# ETH_HMI.net
KiCad netlist of a schematic drawn in Altium Designer
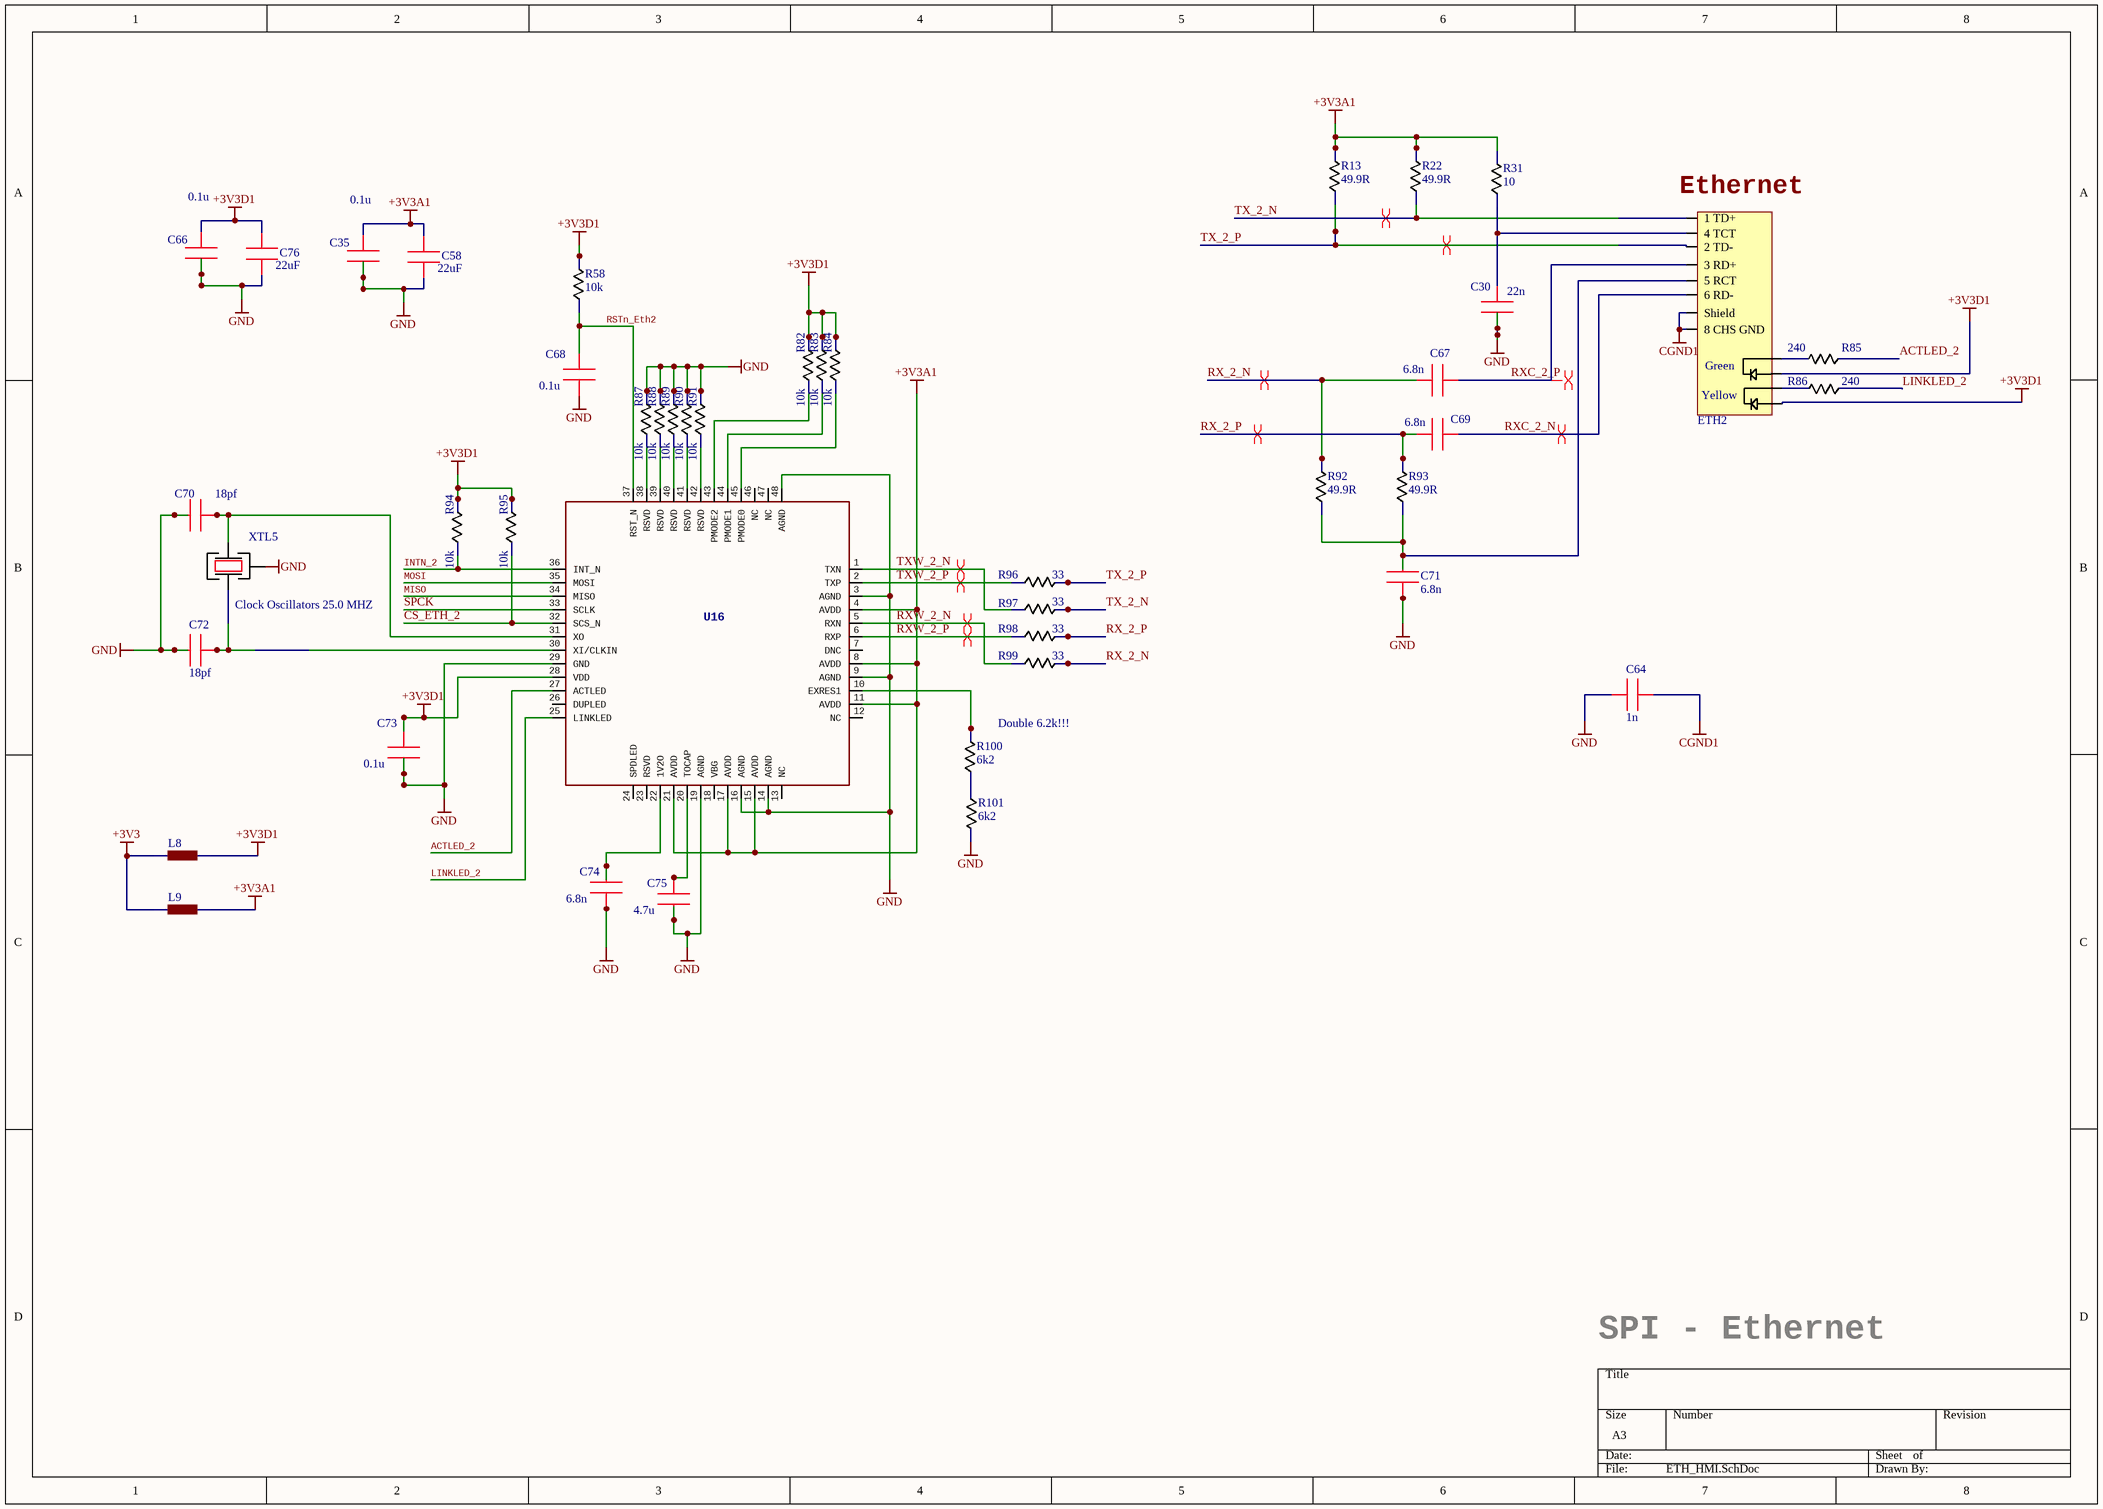
[diagram p0: ETH_HMI.SchDoc]

(export (version "E")
  (design (tool "Eeschema 10.0.6"))
  (components
    (comp (ref "C30")
      (value "22n")
      (footprint "0603")
      (fields (field (name "PART NUMBER") "GRM188R71H223KA01D"))
      (libsource (lib "kontr") (part "0603 CAP"))
    )
    (comp (ref "C35")
      (value "0.1u")
      (footprint "0603")
      (fields (field (name "PART NUMBER") "GRM188R72A104KA35D"))
      (libsource (lib "kontr") (part "0603 CAP"))
    )
    (comp (ref "C58")
      (value "22uF")
      (footprint "1206")
      (fields (field (name "PART NUMBER") "CC206KKX5R7BB226"))
      (libsource (lib "") (part "0805 Cap_1"))
    )
    (comp (ref "C64")
      (value "1n")
      (footprint "1206")
      (fields (field (name "PART NUMBER") "CC1206KKX7RDBB102"))
      (libsource (lib "kontr") (part "0603 CAP"))
    )
    (comp (ref "C66")
      (value "0.1u")
      (footprint "0603")
      (fields (field (name "PART NUMBER") "GRM188R72A104KA35D"))
      (libsource (lib "kontr") (part "0603 CAP"))
    )
    (comp (ref "C67")
      (value "6.8n")
      (footprint "0603")
      (fields (field (name "PART NUMBER") "CC0603KRX7R9BB682"))
      (libsource (lib "") (part "0603 CAP_1"))
    )
    (comp (ref "C68")
      (value "0.1u")
      (footprint "0603")
      (fields (field (name "PART NUMBER") "GRM188R72A104KA35D"))
      (libsource (lib "kontr") (part "0603 CAP"))
    )
    (comp (ref "C69")
      (value "6.8n")
      (footprint "0603")
      (fields (field (name "PART NUMBER") "CC0603KRX7R9BB682"))
      (libsource (lib "") (part "0603 CAP_1"))
    )
    (comp (ref "C70")
      (value "18pf")
      (footprint "0603")
      (fields (field (name "PART NUMBER") "GRM1885C1H180JA01D"))
      (libsource (lib "") (part "0603 CAP_1"))
    )
    (comp (ref "C71")
      (value "6.8n")
      (footprint "0603")
      (fields (field (name "PART NUMBER") "CC0603KRX7R9BB682"))
      (libsource (lib "kontr") (part "0603 CAP"))
    )
    (comp (ref "C72")
      (value "18pf")
      (footprint "0603")
      (fields (field (name "PART NUMBER") "GRM1885C1H180JA01D"))
      (libsource (lib "") (part "0603 CAP_1"))
    )
    (comp (ref "C73")
      (value "0.1u")
      (footprint "0603")
      (fields (field (name "PART NUMBER") "GRM188R72A104KA35D"))
      (libsource (lib "kontr") (part "0603 CAP"))
    )
    (comp (ref "C74")
      (value "6.8n")
      (footprint "0603")
      (fields (field (name "PART NUMBER") "CC0603KRX7R9BB682"))
      (libsource (lib "kontr") (part "0603 CAP"))
    )
    (comp (ref "C75")
      (value "4.7u")
      (footprint "0603")
      (fields (field (name "PART NUMBER") "CC0603KRX5R7BB475"))
      (libsource (lib "kontr") (part "0603 CAP"))
    )
    (comp (ref "C76")
      (value "22uF")
      (footprint "1206")
      (fields (field (name "PART NUMBER") "CC206KKX5R7BB226"))
      (libsource (lib "kontr") (part "0805 Cap"))
    )
    (comp (ref "ETH2")
      (value "~")
      (footprint "RJ45")
      (fields (field (name "PART NUMBER") "J0011D21BNL"))
      (libsource (lib "kontr") (part "J0011D21BNL"))
    )
    (comp (ref "L8")
      (value "~")
      (footprint "0805")
      (fields (field (name "PART NUMBER") "BLM41PG102SN1L"))
      (libsource (lib "kontr") (part "BLM21PG220SN1D"))
    )
    (comp (ref "L9")
      (value "~")
      (footprint "0805")
      (fields (field (name "PART NUMBER") "BLM41PG102SN1L"))
      (libsource (lib "kontr") (part "BLM21PG220SN1D"))
    )
    (comp (ref "R13")
      (value "49.9R")
      (footprint "0603")
      (fields (field (name "PART NUMBER") "RC0603FR-0749R9"))
      (libsource (lib "kontr") (part "0603 RES"))
    )
    (comp (ref "R22")
      (value "49.9R")
      (footprint "0603")
      (fields (field (name "PART NUMBER") "RC0603FR-0749R9"))
      (libsource (lib "kontr") (part "0603 RES"))
    )
    (comp (ref "R31")
      (value "10")
      (footprint "0603")
      (fields (field (name "PART NUMBER") "CRCW060310R0FKEA"))
      (libsource (lib "kontr") (part "0603 RES"))
    )
    (comp (ref "R58")
      (value "10k")
      (footprint "0603")
      (fields (field (name "PART NUMBER") "RC0603JR-0710K"))
      (libsource (lib "kontr") (part "0603 RES"))
    )
    (comp (ref "R82")
      (value "10k")
      (footprint "0603")
      (fields (field (name "PART NUMBER") "RC0603JR-0710K"))
      (libsource (lib "kontr") (part "0603 RES"))
    )
    (comp (ref "R83")
      (value "10k")
      (footprint "0603")
      (fields (field (name "PART NUMBER") "RC0603JR-0710K"))
      (libsource (lib "kontr") (part "0603 RES"))
    )
    (comp (ref "R84")
      (value "10k")
      (footprint "0603")
      (fields (field (name "PART NUMBER") "RC0603JR-0710K"))
      (libsource (lib "kontr") (part "0603 RES"))
    )
    (comp (ref "R85")
      (value "240")
      (footprint "0603")
      (fields (field (name "PART NUMBER") "RC0603FR-07240RL"))
      (libsource (lib "kontr") (part "0603 RES"))
    )
    (comp (ref "R86")
      (value "240")
      (footprint "0603")
      (fields (field (name "PART NUMBER") "RC0603FR-07240RL"))
      (libsource (lib "kontr") (part "0603 RES"))
    )
    (comp (ref "R87")
      (value "10k")
      (footprint "0603")
      (fields (field (name "PART NUMBER") "RC0603JR-0710K"))
      (libsource (lib "kontr") (part "0603 RES"))
    )
    (comp (ref "R88")
      (value "10k")
      (footprint "0603")
      (fields (field (name "PART NUMBER") "RC0603JR-0710K"))
      (libsource (lib "kontr") (part "0603 RES"))
    )
    (comp (ref "R89")
      (value "10k")
      (footprint "0603")
      (fields (field (name "PART NUMBER") "RC0603JR-0710K"))
      (libsource (lib "kontr") (part "0603 RES"))
    )
    (comp (ref "R90")
      (value "10k")
      (footprint "0603")
      (fields (field (name "PART NUMBER") "RC0603JR-0710K"))
      (libsource (lib "kontr") (part "0603 RES"))
    )
    (comp (ref "R91")
      (value "10k")
      (footprint "0603")
      (fields (field (name "PART NUMBER") "RC0603JR-0710K"))
      (libsource (lib "kontr") (part "0603 RES"))
    )
    (comp (ref "R92")
      (value "49.9R")
      (footprint "0603")
      (fields (field (name "PART NUMBER") "RC0603FR-0749R9"))
      (libsource (lib "kontr") (part "0603 RES"))
    )
    (comp (ref "R93")
      (value "49.9R")
      (footprint "0603")
      (fields (field (name "PART NUMBER") "RC0603FR-0749R9"))
      (libsource (lib "kontr") (part "0603 RES"))
    )
    (comp (ref "R94")
      (value "10k")
      (footprint "0603")
      (fields (field (name "PART NUMBER") "RC0603JR-0710K"))
      (libsource (lib "kontr") (part "0603 RES"))
    )
    (comp (ref "R95")
      (value "10k")
      (footprint "0603")
      (fields (field (name "PART NUMBER") "RC0603JR-0710K"))
      (libsource (lib "kontr") (part "0603 RES"))
    )
    (comp (ref "R96")
      (value "33")
      (footprint "0603")
      (fields (field (name "PART NUMBER") "RC0603FR-0733RL"))
      (libsource (lib "kontr") (part "0603 RES"))
    )
    (comp (ref "R97")
      (value "33")
      (footprint "0603")
      (fields (field (name "PART NUMBER") "RC0603FR-0733RL"))
      (libsource (lib "kontr") (part "0603 RES"))
    )
    (comp (ref "R98")
      (value "33")
      (footprint "0603")
      (fields (field (name "PART NUMBER") "RC0603FR-0733RL"))
      (libsource (lib "kontr") (part "0603 RES"))
    )
    (comp (ref "R99")
      (value "33")
      (footprint "0603")
      (fields (field (name "PART NUMBER") "RC0603FR-0733RL"))
      (libsource (lib "kontr") (part "0603 RES"))
    )
    (comp (ref "R100")
      (value "6k2")
      (footprint "0603")
      (fields (field (name "PART NUMBER") "RC0603JR-076K2L"))
      (libsource (lib "kontr") (part "0603 RES"))
    )
    (comp (ref "R101")
      (value "6k2")
      (footprint "0603")
      (fields (field (name "PART NUMBER") "RC0603JR-076K2L"))
      (libsource (lib "kontr") (part "Resistor 0805"))
    )
    (comp (ref "U16")
      (value "~")
      (footprint "LQFP 48")
      (fields (field (name "PART NUMBER") "W5500"))
      (libsource (lib "W5500") (part "W5500"))
    )
    (comp (ref "XTL5")
      (value "~")
      (footprint "KX-7 XTAL")
      (fields
        (field (name "PART DESCRIPTION") "Clock Oscillators 25.0 MHZ")
        (field (name "PART NUMBER") "Geyer KX-7 25.0 MHz")
      )
      (libsource (lib "kontr") (part "KX-7"))
    )
  )
  (nets
    (net (code "1") (name "+3V3") (class "Default")
      (node (ref "L8") (pin "1") (pintype "passive"))
      (node (ref "L9") (pin "1") (pintype "passive"))
    )
    (net (code "2") (name "+3V3A1") (class "Default")
      (node (ref "C35") (pin "1") (pinfunction "1_1") (pintype "passive"))
      (node (ref "C58") (pin "2") (pinfunction "2_2") (pintype "passive"))
      (node (ref "L9") (pin "2") (pintype "passive"))
      (node (ref "R13") (pin "2") (pintype "passive"))
      (node (ref "R22") (pin "2") (pintype "passive"))
      (node (ref "R31") (pin "2") (pintype "passive"))
      (node (ref "U16") (pin "11") (pinfunction "AVDD_11") (pintype "passive"))
      (node (ref "U16") (pin "15") (pinfunction "AVDD_15") (pintype "passive"))
      (node (ref "U16") (pin "17") (pinfunction "AVDD_17") (pintype "passive"))
      (node (ref "U16") (pin "21") (pinfunction "AVDD_21") (pintype "passive"))
      (node (ref "U16") (pin "4") (pinfunction "AVDD_4") (pintype "passive"))
      (node (ref "U16") (pin "8") (pinfunction "AVDD_8") (pintype "passive"))
    )
    (net (code "3") (name "+3V3D1") (class "Default")
      (node (ref "C66") (pin "1") (pinfunction "1_1") (pintype "passive"))
      (node (ref "C73") (pin "1") (pinfunction "1_1") (pintype "passive"))
      (node (ref "C76") (pin "2") (pinfunction "2_2") (pintype "passive"))
      (node (ref "ETH2") (pin "12") (pinfunction "LDYE_12") (pintype "passive"))
      (node (ref "ETH2") (pin "9") (pinfunction "LDGr_9") (pintype "passive"))
      (node (ref "L8") (pin "2") (pintype "passive"))
      (node (ref "R58") (pin "2") (pintype "passive"))
      (node (ref "R82") (pin "2") (pintype "passive"))
      (node (ref "R83") (pin "2") (pintype "passive"))
      (node (ref "R84") (pin "2") (pintype "passive"))
      (node (ref "R94") (pin "2") (pintype "passive"))
      (node (ref "R95") (pin "2") (pintype "passive"))
      (node (ref "U16") (pin "28") (pinfunction "VDD_28") (pintype "passive"))
    )
    (net (code "4") (name "/ACTLED_2") (class "Default")
      (node (ref "R85") (pin "1") (pintype "passive"))
      (node (ref "U16") (pin "27") (pinfunction "ACTLED_27") (pintype "passive"))
    )
    (net (code "5") (name "/CS_ETH_2") (class "Default")
      (node (ref "R95") (pin "1") (pintype "passive"))
      (node (ref "U16") (pin "32") (pinfunction "SCS_N_32") (pintype "passive"))
    )
    (net (code "6") (name "/INTN_2") (class "Default")
      (node (ref "R94") (pin "1") (pintype "passive"))
      (node (ref "U16") (pin "36") (pinfunction "INT_N_36") (pintype "passive"))
    )
    (net (code "7") (name "/LINKLED_2") (class "Default")
      (node (ref "R86") (pin "1") (pintype "passive"))
      (node (ref "U16") (pin "25") (pinfunction "LINKLED_25") (pintype "passive"))
    )
    (net (code "8") (name "/MISO") (class "Default")
      (node (ref "U16") (pin "34") (pinfunction "MISO_34") (pintype "passive"))
    )
    (net (code "9") (name "/MOSI") (class "Default")
      (node (ref "U16") (pin "35") (pinfunction "MOSI_35") (pintype "passive"))
    )
    (net (code "10") (name "/RSTn_Eth2") (class "Default")
      (node (ref "C68") (pin "1") (pinfunction "1_1") (pintype "passive"))
      (node (ref "R58") (pin "1") (pintype "passive"))
      (node (ref "U16") (pin "37") (pinfunction "RST_N_37") (pintype "passive"))
    )
    (net (code "11") (name "/RXC_2_N") (class "Default")
      (node (ref "C69") (pin "2") (pinfunction "2_2") (pintype "passive"))
      (node (ref "ETH2") (pin "6") (pinfunction "6_RD-_6") (pintype "passive"))
    )
    (net (code "12") (name "/RXC_2_P") (class "Default")
      (node (ref "C67") (pin "2") (pinfunction "2_2") (pintype "passive"))
      (node (ref "ETH2") (pin "3") (pinfunction "3_RD+_3") (pintype "passive"))
    )
    (net (code "13") (name "/RXW_2_N") (class "Default")
      (node (ref "R99") (pin "1") (pintype "passive"))
      (node (ref "U16") (pin "5") (pinfunction "RXN_5") (pintype "passive"))
    )
    (net (code "14") (name "/RXW_2_P") (class "Default")
      (node (ref "R98") (pin "1") (pintype "passive"))
      (node (ref "U16") (pin "6") (pinfunction "RXP_6") (pintype "passive"))
    )
    (net (code "15") (name "/RX_2_N") (class "Default")
      (node (ref "C67") (pin "1") (pinfunction "1_1") (pintype "passive"))
      (node (ref "R92") (pin "2") (pintype "passive"))
      (node (ref "R99") (pin "2") (pintype "passive"))
    )
    (net (code "16") (name "/RX_2_P") (class "Default")
      (node (ref "C69") (pin "1") (pinfunction "1_1") (pintype "passive"))
      (node (ref "R93") (pin "2") (pintype "passive"))
      (node (ref "R98") (pin "2") (pintype "passive"))
    )
    (net (code "17") (name "/SPCK") (class "Default")
      (node (ref "U16") (pin "33") (pinfunction "SCLK_33") (pintype "passive"))
    )
    (net (code "18") (name "/TXW_2_N") (class "Default")
      (node (ref "R97") (pin "1") (pintype "passive"))
      (node (ref "U16") (pin "1") (pinfunction "TXN_1") (pintype "passive"))
    )
    (net (code "19") (name "/TXW_2_P") (class "Default")
      (node (ref "R96") (pin "1") (pintype "passive"))
      (node (ref "U16") (pin "2") (pinfunction "TXP_2") (pintype "passive"))
    )
    (net (code "20") (name "/TX_2_N") (class "Default")
      (node (ref "ETH2") (pin "1") (pinfunction "1_TD+_1") (pintype "passive"))
      (node (ref "R22") (pin "1") (pintype "passive"))
      (node (ref "R97") (pin "2") (pintype "passive"))
    )
    (net (code "21") (name "/TX_2_P") (class "Default")
      (node (ref "ETH2") (pin "2") (pinfunction "2_TD-_2") (pintype "passive"))
      (node (ref "R13") (pin "1") (pintype "passive"))
      (node (ref "R96") (pin "2") (pintype "passive"))
    )
    (net (code "22") (name "CGND1") (class "Default")
      (node (ref "C64") (pin "2") (pinfunction "2_2") (pintype "passive"))
      (node (ref "ETH2") (pin "8") (pinfunction "8_CHS_GND_8") (pintype "passive"))
      (node (ref "ETH2") (pin "SHIELD") (pinfunction "Shield_SHIELD") (pintype "passive"))
    )
    (net (code "23") (name "GND") (class "Default")
      (node (ref "C30") (pin "2") (pinfunction "2_2") (pintype "passive"))
      (node (ref "C35") (pin "2") (pinfunction "2_2") (pintype "passive"))
      (node (ref "C58") (pin "1") (pinfunction "1_1") (pintype "passive"))
      (node (ref "C64") (pin "1") (pinfunction "1_1") (pintype "passive"))
      (node (ref "C66") (pin "2") (pinfunction "2_2") (pintype "passive"))
      (node (ref "C68") (pin "2") (pinfunction "2_2") (pintype "passive"))
      (node (ref "C70") (pin "1") (pinfunction "1_1") (pintype "passive"))
      (node (ref "C71") (pin "2") (pinfunction "2_2") (pintype "passive"))
      (node (ref "C72") (pin "1") (pinfunction "1_1") (pintype "passive"))
      (node (ref "C73") (pin "2") (pinfunction "2_2") (pintype "passive"))
      (node (ref "C74") (pin "2") (pinfunction "2_2") (pintype "passive"))
      (node (ref "C75") (pin "2") (pinfunction "2_2") (pintype "passive"))
      (node (ref "C76") (pin "1") (pinfunction "1_1") (pintype "passive"))
      (node (ref "R101") (pin "2") (pintype "passive"))
      (node (ref "R87") (pin "2") (pintype "passive"))
      (node (ref "R88") (pin "2") (pintype "passive"))
      (node (ref "R89") (pin "2") (pintype "passive"))
      (node (ref "R90") (pin "2") (pintype "passive"))
      (node (ref "R91") (pin "2") (pintype "passive"))
      (node (ref "U16") (pin "14") (pinfunction "AGND_14") (pintype "passive"))
      (node (ref "U16") (pin "16") (pinfunction "AGND_16") (pintype "passive"))
      (node (ref "U16") (pin "19") (pinfunction "AGND_19") (pintype "passive"))
      (node (ref "U16") (pin "29") (pinfunction "GND_29") (pintype "passive"))
      (node (ref "U16") (pin "3") (pinfunction "AGND_3") (pintype "passive"))
      (node (ref "U16") (pin "48") (pinfunction "AGND_48") (pintype "passive"))
      (node (ref "U16") (pin "9") (pinfunction "AGND_9") (pintype "passive"))
      (node (ref "XTL5") (pin "2") (pinfunction "2_2") (pintype "passive"))
    )
    (net (code "24") (name "Net-(ETH2-4_TCT)") (class "Default")
      (node (ref "C30") (pin "1") (pinfunction "1_1") (pintype "passive"))
      (node (ref "ETH2") (pin "4") (pinfunction "4_TCT_4") (pintype "passive"))
      (node (ref "R31") (pin "1") (pintype "passive"))
    )
    (net (code "25") (name "Net-(ETH2-5_RCT)") (class "Default")
      (node (ref "C71") (pin "1") (pinfunction "1_1") (pintype "passive"))
      (node (ref "ETH2") (pin "5") (pinfunction "5_RCT_5") (pintype "passive"))
      (node (ref "R92") (pin "1") (pintype "passive"))
      (node (ref "R93") (pin "1") (pintype "passive"))
    )
    (net (code "26") (name "Net-(ETH2-LDGr-Pad10)") (class "Default")
      (node (ref "ETH2") (pin "10") (pinfunction "LDGr_10") (pintype "passive"))
      (node (ref "R85") (pin "2") (pintype "passive"))
    )
    (net (code "27") (name "Net-(ETH2-LDYE-Pad11)") (class "Default")
      (node (ref "ETH2") (pin "11") (pinfunction "LDYE_11") (pintype "passive"))
      (node (ref "R86") (pin "2") (pintype "passive"))
    )
    (net (code "28") (name "Net-(R87-Pad1)") (class "Default")
      (node (ref "R87") (pin "1") (pintype "passive"))
      (node (ref "U16") (pin "38") (pinfunction "RSVD_38") (pintype "passive"))
    )
    (net (code "29") (name "Net-(R88-Pad1)") (class "Default")
      (node (ref "R88") (pin "1") (pintype "passive"))
      (node (ref "U16") (pin "39") (pinfunction "RSVD_39") (pintype "passive"))
    )
    (net (code "30") (name "Net-(R89-Pad1)") (class "Default")
      (node (ref "R89") (pin "1") (pintype "passive"))
      (node (ref "U16") (pin "40") (pinfunction "RSVD_40") (pintype "passive"))
    )
    (net (code "31") (name "Net-(R90-Pad1)") (class "Default")
      (node (ref "R90") (pin "1") (pintype "passive"))
      (node (ref "U16") (pin "41") (pinfunction "RSVD_41") (pintype "passive"))
    )
    (net (code "32") (name "Net-(R91-Pad1)") (class "Default")
      (node (ref "R91") (pin "1") (pintype "passive"))
      (node (ref "U16") (pin "42") (pinfunction "RSVD_42") (pintype "passive"))
    )
    (net (code "33") (name "Net-(R100-Pad1)") (class "Default")
      (node (ref "R100") (pin "1") (pintype "passive"))
      (node (ref "R101") (pin "1") (pintype "passive"))
    )
    (net (code "34") (name "Net-(U16-1V2O)") (class "Default")
      (node (ref "C74") (pin "1") (pinfunction "1_1") (pintype "passive"))
      (node (ref "U16") (pin "22") (pinfunction "1V2O_22") (pintype "passive"))
    )
    (net (code "35") (name "Net-(U16-EXRES1)") (class "Default")
      (node (ref "R100") (pin "2") (pintype "passive"))
      (node (ref "U16") (pin "10") (pinfunction "EXRES1_10") (pintype "passive"))
    )
    (net (code "36") (name "Net-(U16-PMODE0)") (class "Default")
      (node (ref "R84") (pin "1") (pintype "passive"))
      (node (ref "U16") (pin "45") (pinfunction "PMODE0_45") (pintype "passive"))
    )
    (net (code "37") (name "Net-(U16-PMODE1)") (class "Default")
      (node (ref "R83") (pin "1") (pintype "passive"))
      (node (ref "U16") (pin "44") (pinfunction "PMODE1_44") (pintype "passive"))
    )
    (net (code "38") (name "Net-(U16-PMODE2)") (class "Default")
      (node (ref "R82") (pin "1") (pintype "passive"))
      (node (ref "U16") (pin "43") (pinfunction "PMODE2_43") (pintype "passive"))
    )
    (net (code "39") (name "Net-(U16-TOCAP)") (class "Default")
      (node (ref "C75") (pin "1") (pinfunction "1_1") (pintype "passive"))
      (node (ref "U16") (pin "20") (pinfunction "TOCAP_20") (pintype "passive"))
    )
    (net (code "40") (name "Net-(U16-XI{slash}CLKIN)") (class "Default")
      (node (ref "C72") (pin "2") (pinfunction "2_2") (pintype "passive"))
      (node (ref "U16") (pin "30") (pinfunction "XI/CLKIN_30") (pintype "passive"))
      (node (ref "XTL5") (pin "1") (pinfunction "5_1") (pintype "passive"))
    )
    (net (code "41") (name "Net-(U16-XO)") (class "Default")
      (node (ref "C70") (pin "2") (pinfunction "2_2") (pintype "passive"))
      (node (ref "U16") (pin "31") (pinfunction "XO_31") (pintype "passive"))
      (node (ref "XTL5") (pin "3") (pinfunction "5_3") (pintype "passive"))
    )
    (net (code "42") (name "unconnected-(U16-DNC-Pad7)") (class "Default")
      (node (ref "U16") (pin "7") (pinfunction "DNC_7") (pintype "passive"))
    )
    (net (code "43") (name "unconnected-(U16-DUPLED-Pad26)") (class "Default")
      (node (ref "U16") (pin "26") (pinfunction "DUPLED_26") (pintype "passive"))
    )
    (net (code "44") (name "unconnected-(U16-NC-Pad12)") (class "Default")
      (node (ref "U16") (pin "12") (pinfunction "NC_12") (pintype "passive"))
    )
    (net (code "45") (name "unconnected-(U16-NC-Pad13)") (class "Default")
      (node (ref "U16") (pin "13") (pinfunction "NC_13") (pintype "passive"))
    )
    (net (code "46") (name "unconnected-(U16-NC-Pad46)") (class "Default")
      (node (ref "U16") (pin "46") (pinfunction "NC_46") (pintype "passive"))
    )
    (net (code "47") (name "unconnected-(U16-NC-Pad47)") (class "Default")
      (node (ref "U16") (pin "47") (pinfunction "NC_47") (pintype "passive"))
    )
    (net (code "48") (name "unconnected-(U16-RSVD-Pad23)") (class "Default")
      (node (ref "U16") (pin "23") (pinfunction "RSVD_23") (pintype "passive"))
    )
    (net (code "49") (name "unconnected-(U16-SPDLED-Pad24)") (class "Default")
      (node (ref "U16") (pin "24") (pinfunction "SPDLED_24") (pintype "passive"))
    )
    (net (code "50") (name "unconnected-(U16-VBG-Pad18)") (class "Default")
      (node (ref "U16") (pin "18") (pinfunction "VBG_18") (pintype "passive"))
    )
  )
)
